# bottom.net
KiCad netlist of a schematic drawn in EAGLE
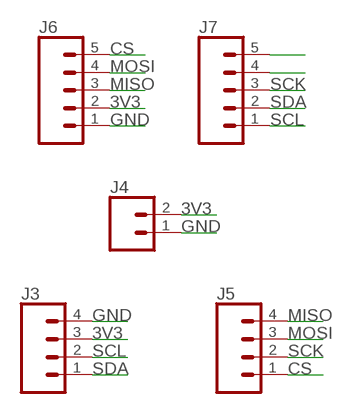
[diagram p0: schematic, sheet 1]

(export (version "E")
  (design (tool "Eeschema 10.0.6"))
  (components
    (comp (ref "J3")
      (value "CONN_041X04_NO_SILK")
      (footprint "eagle-import:1X04_NO_SILK")
      (libsource (lib "eagle-import") (part "CONN_041X04_NO_SILK"))
    )
    (comp (ref "J4")
      (value "CONN_021X02_NO_SILK")
      (footprint "eagle-import:1X02_NO_SILK")
      (libsource (lib "eagle-import") (part "CONN_021X02_NO_SILK"))
    )
    (comp (ref "J5")
      (value "CONN_041X04_NO_SILK")
      (footprint "eagle-import:1X04_NO_SILK")
      (libsource (lib "eagle-import") (part "CONN_041X04_NO_SILK"))
    )
    (comp (ref "J6")
      (value "CONN_05NO_SILK")
      (footprint "eagle-import:1X05_NO_SILK")
      (libsource (lib "eagle-import") (part "CONN_05NO_SILK"))
    )
    (comp (ref "J7")
      (value "CONN_05NO_SILK")
      (footprint "eagle-import:1X05_NO_SILK")
      (libsource (lib "eagle-import") (part "CONN_05NO_SILK"))
    )
  )
  (nets
    (net (code "1") (name "/3V3") (class "Default")
      (node (ref "J3") (pin "3") (pinfunction "3_3") (pintype "passive"))
      (node (ref "J4") (pin "2") (pinfunction "2_2") (pintype "passive"))
      (node (ref "J6") (pin "2") (pinfunction "2_2") (pintype "passive"))
    )
    (net (code "2") (name "/CS") (class "Default")
      (node (ref "J5") (pin "1") (pinfunction "1_1") (pintype "passive"))
      (node (ref "J6") (pin "5") (pinfunction "5_5") (pintype "passive"))
    )
    (net (code "3") (name "/GND") (class "Default")
      (node (ref "J3") (pin "4") (pinfunction "4_4") (pintype "passive"))
      (node (ref "J4") (pin "1") (pinfunction "1_1") (pintype "passive"))
      (node (ref "J6") (pin "1") (pinfunction "1_1") (pintype "passive"))
    )
    (net (code "4") (name "/MISO") (class "Default")
      (node (ref "J5") (pin "4") (pinfunction "4_4") (pintype "passive"))
      (node (ref "J6") (pin "3") (pinfunction "3_3") (pintype "passive"))
    )
    (net (code "5") (name "/MOSI") (class "Default")
      (node (ref "J5") (pin "3") (pinfunction "3_3") (pintype "passive"))
      (node (ref "J6") (pin "4") (pinfunction "4_4") (pintype "passive"))
    )
    (net (code "6") (name "/SCK") (class "Default")
      (node (ref "J5") (pin "2") (pinfunction "2_2") (pintype "passive"))
      (node (ref "J7") (pin "3") (pinfunction "3_3") (pintype "passive"))
    )
    (net (code "7") (name "/SCL") (class "Default")
      (node (ref "J3") (pin "2") (pinfunction "2_2") (pintype "passive"))
      (node (ref "J7") (pin "1") (pinfunction "1_1") (pintype "passive"))
    )
    (net (code "8") (name "/SDA") (class "Default")
      (node (ref "J3") (pin "1") (pinfunction "1_1") (pintype "passive"))
      (node (ref "J7") (pin "2") (pinfunction "2_2") (pintype "passive"))
    )
    (net (code "9") (name "unconnected-(J7-Pad4)") (class "Default")
      (node (ref "J7") (pin "4") (pinfunction "4_4") (pintype "passive"))
    )
    (net (code "10") (name "unconnected-(J7-Pad5)") (class "Default")
      (node (ref "J7") (pin "5") (pinfunction "5_5") (pintype "passive"))
    )
  )
)
